# schemat.net
KiCad netlist of a schematic drawn in EAGLE
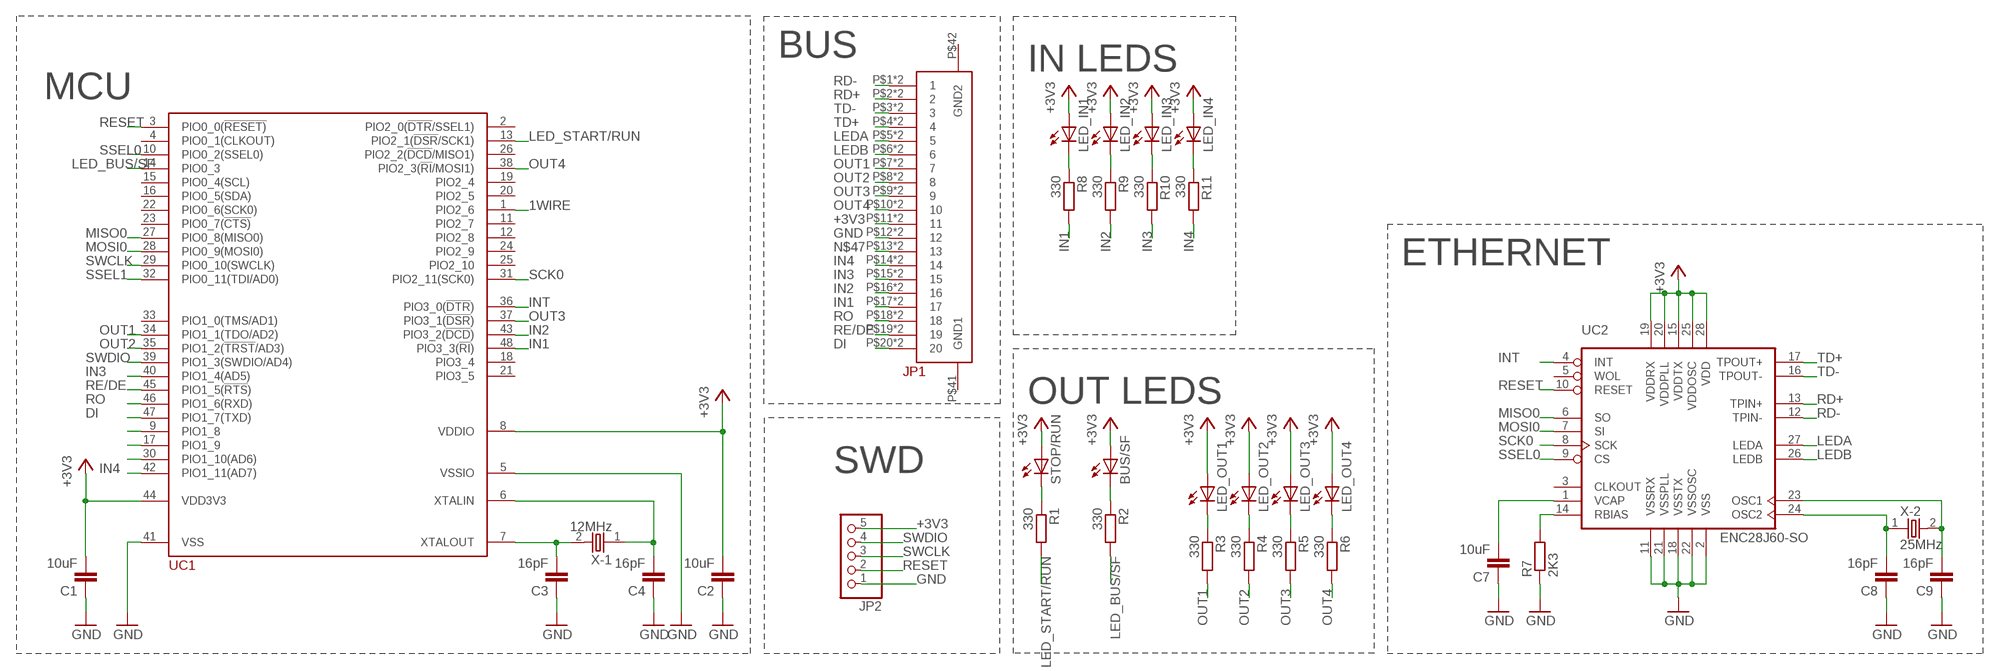
[diagram p0: schematic, sheet 1]

(export (version "E")
  (design (tool "Eeschema 10.0.6"))
  (components
    (comp (ref "BUS/SF")
      (value "LED3MM")
      (footprint "eagle-import:LED3MM")
      (libsource (lib "eagle-import") (part "LED3MM"))
    )
    (comp (ref "C1")
      (value "10uF")
      (footprint "eagle-import:C0805")
      (libsource (lib "eagle-import") (part "C-0805"))
    )
    (comp (ref "C2")
      (value "10uF")
      (footprint "eagle-import:C0805")
      (libsource (lib "eagle-import") (part "C-0805"))
    )
    (comp (ref "C3")
      (value "16pF")
      (footprint "eagle-import:C0805")
      (libsource (lib "eagle-import") (part "C-0805"))
    )
    (comp (ref "C4")
      (value "16pF")
      (footprint "eagle-import:C0805")
      (libsource (lib "eagle-import") (part "C-0805"))
    )
    (comp (ref "C7")
      (value "10uF")
      (footprint "eagle-import:C0805")
      (libsource (lib "eagle-import") (part "C-0805"))
    )
    (comp (ref "C8")
      (value "16pF")
      (footprint "eagle-import:C0805")
      (libsource (lib "eagle-import") (part "C-0805"))
    )
    (comp (ref "C9")
      (value "16pF")
      (footprint "eagle-import:C0805")
      (libsource (lib "eagle-import") (part "C-0805"))
    )
    (comp (ref "JP1")
      (value "FFC(FPC)_ZIF_20_PINV")
      (footprint "eagle-import:PCA-2C-20-V-3")
      (libsource (lib "eagle-import") (part "FFC(FPC)_ZIF_20_PINV"))
    )
    (comp (ref "JP2")
      (value "PINHD-1X5")
      (footprint "eagle-import:1X05")
      (libsource (lib "eagle-import") (part "PINHD-1X5"))
    )
    (comp (ref "LED_IN1")
      (value "LED3MM")
      (footprint "eagle-import:LED3MM")
      (libsource (lib "eagle-import") (part "LED3MM"))
    )
    (comp (ref "LED_IN2")
      (value "LED3MM")
      (footprint "eagle-import:LED3MM")
      (libsource (lib "eagle-import") (part "LED3MM"))
    )
    (comp (ref "LED_IN3")
      (value "LED3MM")
      (footprint "eagle-import:LED3MM")
      (libsource (lib "eagle-import") (part "LED3MM"))
    )
    (comp (ref "LED_IN4")
      (value "LED3MM")
      (footprint "eagle-import:LED3MM")
      (libsource (lib "eagle-import") (part "LED3MM"))
    )
    (comp (ref "LED_OUT1")
      (value "LED3MM")
      (footprint "eagle-import:LED3MM")
      (libsource (lib "eagle-import") (part "LED3MM"))
    )
    (comp (ref "LED_OUT2")
      (value "LED3MM")
      (footprint "eagle-import:LED3MM")
      (libsource (lib "eagle-import") (part "LED3MM"))
    )
    (comp (ref "LED_OUT3")
      (value "LED3MM")
      (footprint "eagle-import:LED3MM")
      (libsource (lib "eagle-import") (part "LED3MM"))
    )
    (comp (ref "LED_OUT4")
      (value "LED3MM")
      (footprint "eagle-import:LED3MM")
      (libsource (lib "eagle-import") (part "LED3MM"))
    )
    (comp (ref "R1")
      (value "330")
      (footprint "eagle-import:R0805W")
      (libsource (lib "eagle-import") (part "R-0805W"))
    )
    (comp (ref "R2")
      (value "330")
      (footprint "eagle-import:R0805W")
      (libsource (lib "eagle-import") (part "R-0805W"))
    )
    (comp (ref "R3")
      (value "330")
      (footprint "eagle-import:R0805W")
      (libsource (lib "eagle-import") (part "R-0805W"))
    )
    (comp (ref "R4")
      (value "330")
      (footprint "eagle-import:R0805W")
      (libsource (lib "eagle-import") (part "R-0805W"))
    )
    (comp (ref "R5")
      (value "330")
      (footprint "eagle-import:R0805W")
      (libsource (lib "eagle-import") (part "R-0805W"))
    )
    (comp (ref "R6")
      (value "330")
      (footprint "eagle-import:R0805W")
      (libsource (lib "eagle-import") (part "R-0805W"))
    )
    (comp (ref "R7")
      (value "2K3")
      (footprint "eagle-import:R0805")
      (libsource (lib "eagle-import") (part "R-0805"))
    )
    (comp (ref "R8")
      (value "330")
      (footprint "eagle-import:R0805W")
      (libsource (lib "eagle-import") (part "R-0805W"))
    )
    (comp (ref "R9")
      (value "330")
      (footprint "eagle-import:R0805W")
      (libsource (lib "eagle-import") (part "R-0805W"))
    )
    (comp (ref "R10")
      (value "330")
      (footprint "eagle-import:R0805W")
      (libsource (lib "eagle-import") (part "R-0805W"))
    )
    (comp (ref "R11")
      (value "330")
      (footprint "eagle-import:R0805W")
      (libsource (lib "eagle-import") (part "R-0805W"))
    )
    (comp (ref "STOP/RUN")
      (value "LED3MM")
      (footprint "eagle-import:LED3MM")
      (libsource (lib "eagle-import") (part "LED3MM"))
    )
    (comp (ref "UC1")
      (value "NXP-LPC111X")
      (footprint "eagle-import:LQFP48")
      (libsource (lib "eagle-import") (part "NXP-LPC111X"))
    )
    (comp (ref "UC2")
      (value "ENC28J60-SO")
      (footprint "eagle-import:SO28W")
      (libsource (lib "eagle-import") (part "ENC28J60-SO"))
    )
    (comp (ref "X-1")
      (value "12MHz")
      (footprint "eagle-import:HC49UP")
      (libsource (lib "eagle-import") (part "CRISTAL_SMD"))
    )
    (comp (ref "X-2")
      (value "25MHz")
      (footprint "eagle-import:HC49UP")
      (libsource (lib "eagle-import") (part "CRISTAL_SMD"))
    )
  )
  (nets
    (net (code "1") (name "+3V3") (class "Default")
      (node (ref "BUS/SF") (pin "A") (pinfunction "A_A") (pintype "passive"))
      (node (ref "C1") (pin "2") (pinfunction "2_2") (pintype "passive"))
      (node (ref "C2") (pin "2") (pinfunction "2_2") (pintype "passive"))
      (node (ref "JP1") (pin "P$11") (pinfunction "11_P$11") (pintype "bidirectional"))
      (node (ref "JP1") (pin "P$31") (pinfunction "11_P$31") (pintype "bidirectional"))
      (node (ref "JP2") (pin "5") (pinfunction "5_5") (pintype "passive"))
      (node (ref "LED_IN1") (pin "A") (pinfunction "A_A") (pintype "passive"))
      (node (ref "LED_IN2") (pin "A") (pinfunction "A_A") (pintype "passive"))
      (node (ref "LED_IN3") (pin "A") (pinfunction "A_A") (pintype "passive"))
      (node (ref "LED_IN4") (pin "A") (pinfunction "A_A") (pintype "passive"))
      (node (ref "LED_OUT1") (pin "A") (pinfunction "A_A") (pintype "passive"))
      (node (ref "LED_OUT2") (pin "A") (pinfunction "A_A") (pintype "passive"))
      (node (ref "LED_OUT3") (pin "A") (pinfunction "A_A") (pintype "passive"))
      (node (ref "LED_OUT4") (pin "A") (pinfunction "A_A") (pintype "passive"))
      (node (ref "STOP/RUN") (pin "A") (pinfunction "A_A") (pintype "passive"))
      (node (ref "UC1") (pin "44") (pinfunction "VDD3V3_44") (pintype "bidirectional"))
      (node (ref "UC1") (pin "8") (pinfunction "VDDIO_8") (pintype "bidirectional"))
      (node (ref "UC2") (pin "15") (pinfunction "VDDTX_15") (pintype "power_in"))
      (node (ref "UC2") (pin "19") (pinfunction "VDDRX_19") (pintype "power_in"))
      (node (ref "UC2") (pin "20") (pinfunction "VDDPLL_20") (pintype "power_in"))
      (node (ref "UC2") (pin "25") (pinfunction "VDDOSC_25") (pintype "power_in"))
      (node (ref "UC2") (pin "28") (pinfunction "VDD_28") (pintype "power_in"))
    )
    (net (code "2") (name "/1WIRE") (class "Default")
      (node (ref "UC1") (pin "1") (pinfunction "PIO2_6_1") (pintype "bidirectional"))
    )
    (net (code "3") (name "/DI") (class "Default")
      (node (ref "JP1") (pin "P$20") (pinfunction "20_P$20") (pintype "bidirectional"))
      (node (ref "JP1") (pin "P$40") (pinfunction "20_P$40") (pintype "bidirectional"))
      (node (ref "UC1") (pin "47") (pinfunction "PIO1_7(TXD)_47") (pintype "bidirectional"))
    )
    (net (code "4") (name "/IN1") (class "Default")
      (node (ref "JP1") (pin "P$17") (pinfunction "17_P$17") (pintype "bidirectional"))
      (node (ref "JP1") (pin "P$37") (pinfunction "17_P$37") (pintype "bidirectional"))
      (node (ref "R8") (pin "2") (pinfunction "2_2") (pintype "passive"))
      (node (ref "UC1") (pin "48") (pinfunction "PIO3_3(~{RI})_48") (pintype "bidirectional"))
    )
    (net (code "5") (name "/IN2") (class "Default")
      (node (ref "JP1") (pin "P$16") (pinfunction "16_P$16") (pintype "bidirectional"))
      (node (ref "JP1") (pin "P$36") (pinfunction "16_P$36") (pintype "bidirectional"))
      (node (ref "R9") (pin "2") (pinfunction "2_2") (pintype "passive"))
      (node (ref "UC1") (pin "43") (pinfunction "PIO3_2(~{DCD})_43") (pintype "bidirectional"))
    )
    (net (code "6") (name "/IN3") (class "Default")
      (node (ref "JP1") (pin "P$15") (pinfunction "15_P$15") (pintype "bidirectional"))
      (node (ref "JP1") (pin "P$35") (pinfunction "15_P$35") (pintype "bidirectional"))
      (node (ref "R10") (pin "2") (pinfunction "2_2") (pintype "passive"))
      (node (ref "UC1") (pin "40") (pinfunction "PIO1_4(AD5)_40") (pintype "bidirectional"))
    )
    (net (code "7") (name "/IN4") (class "Default")
      (node (ref "JP1") (pin "P$14") (pinfunction "14_P$14") (pintype "bidirectional"))
      (node (ref "JP1") (pin "P$34") (pinfunction "14_P$34") (pintype "bidirectional"))
      (node (ref "R11") (pin "2") (pinfunction "2_2") (pintype "passive"))
      (node (ref "UC1") (pin "42") (pinfunction "PIO1_11(AD7)_42") (pintype "bidirectional"))
    )
    (net (code "8") (name "/INT") (class "Default")
      (node (ref "UC1") (pin "36") (pinfunction "PIO3_0(~{DTR})_36") (pintype "bidirectional"))
      (node (ref "UC2") (pin "4") (pinfunction "INT_4") (pintype "output"))
    )
    (net (code "9") (name "/LEDA") (class "Default")
      (node (ref "JP1") (pin "P$25") (pinfunction "5_P$25") (pintype "bidirectional"))
      (node (ref "JP1") (pin "P$5") (pinfunction "5_P$5") (pintype "bidirectional"))
      (node (ref "UC2") (pin "27") (pinfunction "LEDA_27") (pintype "output"))
    )
    (net (code "10") (name "/LEDB") (class "Default")
      (node (ref "JP1") (pin "P$26") (pinfunction "6_P$26") (pintype "bidirectional"))
      (node (ref "JP1") (pin "P$6") (pinfunction "6_P$6") (pintype "bidirectional"))
      (node (ref "UC2") (pin "26") (pinfunction "LEDB_26") (pintype "output"))
    )
    (net (code "11") (name "/LED_BUS{slash}SF") (class "Default")
      (node (ref "R2") (pin "2") (pinfunction "2_2") (pintype "passive"))
      (node (ref "UC1") (pin "14") (pinfunction "PIO0_3_14") (pintype "bidirectional"))
    )
    (net (code "12") (name "/LED_START{slash}RUN") (class "Default")
      (node (ref "R1") (pin "2") (pinfunction "2_2") (pintype "passive"))
      (node (ref "UC1") (pin "13") (pinfunction "PIO2_1(~{DSR}/SCK1)_13") (pintype "bidirectional"))
    )
    (net (code "13") (name "/MISO0") (class "Default")
      (node (ref "UC1") (pin "27") (pinfunction "PIO0_8(MISO0)_27") (pintype "bidirectional"))
      (node (ref "UC2") (pin "6") (pinfunction "SO_6") (pintype "open_collector"))
    )
    (net (code "14") (name "/MOSI0") (class "Default")
      (node (ref "UC1") (pin "28") (pinfunction "PIO0_9(MOSI0)_28") (pintype "bidirectional"))
      (node (ref "UC2") (pin "7") (pinfunction "SI_7") (pintype "input"))
    )
    (net (code "15") (name "/N$47") (class "Default")
      (node (ref "JP1") (pin "P$13") (pinfunction "13_P$13") (pintype "bidirectional"))
      (node (ref "JP1") (pin "P$33") (pinfunction "13_P$33") (pintype "bidirectional"))
    )
    (net (code "16") (name "/OUT1") (class "Default")
      (node (ref "JP1") (pin "P$27") (pinfunction "7_P$27") (pintype "bidirectional"))
      (node (ref "JP1") (pin "P$7") (pinfunction "7_P$7") (pintype "bidirectional"))
      (node (ref "R3") (pin "2") (pinfunction "2_2") (pintype "passive"))
      (node (ref "UC1") (pin "34") (pinfunction "PIO1_1(TDO/AD2)_34") (pintype "bidirectional"))
    )
    (net (code "17") (name "/OUT2") (class "Default")
      (node (ref "JP1") (pin "P$28") (pinfunction "8_P$28") (pintype "bidirectional"))
      (node (ref "JP1") (pin "P$8") (pinfunction "8_P$8") (pintype "bidirectional"))
      (node (ref "R4") (pin "2") (pinfunction "2_2") (pintype "passive"))
      (node (ref "UC1") (pin "35") (pinfunction "PIO1_2(~{TRST}/AD3)_35") (pintype "bidirectional"))
    )
    (net (code "18") (name "/OUT3") (class "Default")
      (node (ref "JP1") (pin "P$29") (pinfunction "9_P$29") (pintype "bidirectional"))
      (node (ref "JP1") (pin "P$9") (pinfunction "9_P$9") (pintype "bidirectional"))
      (node (ref "R5") (pin "2") (pinfunction "2_2") (pintype "passive"))
      (node (ref "UC1") (pin "37") (pinfunction "PIO3_1(~{DSR})_37") (pintype "bidirectional"))
    )
    (net (code "19") (name "/OUT4") (class "Default")
      (node (ref "JP1") (pin "P$10") (pinfunction "10_P$10") (pintype "bidirectional"))
      (node (ref "JP1") (pin "P$30") (pinfunction "10_P$30") (pintype "bidirectional"))
      (node (ref "R6") (pin "2") (pinfunction "2_2") (pintype "passive"))
      (node (ref "UC1") (pin "38") (pinfunction "PIO2_3(~{RI}/MOSI1)_38") (pintype "bidirectional"))
    )
    (net (code "20") (name "/RD+") (class "Default")
      (node (ref "JP1") (pin "P$2") (pinfunction "2_P$2") (pintype "bidirectional"))
      (node (ref "JP1") (pin "P$22") (pinfunction "2_P$22") (pintype "bidirectional"))
      (node (ref "UC2") (pin "13") (pinfunction "TPIN+_13") (pintype "input"))
    )
    (net (code "21") (name "/RD-") (class "Default")
      (node (ref "JP1") (pin "P$1") (pinfunction "1_P$1") (pintype "bidirectional"))
      (node (ref "JP1") (pin "P$21") (pinfunction "1_P$21") (pintype "bidirectional"))
      (node (ref "UC2") (pin "12") (pinfunction "TPIN-_12") (pintype "input"))
    )
    (net (code "22") (name "/RESET") (class "Default")
      (node (ref "JP2") (pin "2") (pinfunction "2_2") (pintype "passive"))
      (node (ref "UC1") (pin "3") (pinfunction "PIO0_0(~{RESET})_3") (pintype "bidirectional"))
      (node (ref "UC2") (pin "10") (pinfunction "RESET_10") (pintype "input"))
    )
    (net (code "23") (name "/RE{slash}DE") (class "Default")
      (node (ref "JP1") (pin "P$19") (pinfunction "19_P$19") (pintype "bidirectional"))
      (node (ref "JP1") (pin "P$39") (pinfunction "19_P$39") (pintype "bidirectional"))
      (node (ref "UC1") (pin "45") (pinfunction "PIO1_5(~{RTS})_45") (pintype "bidirectional"))
    )
    (net (code "24") (name "/RO") (class "Default")
      (node (ref "JP1") (pin "P$18") (pinfunction "18_P$18") (pintype "bidirectional"))
      (node (ref "JP1") (pin "P$38") (pinfunction "18_P$38") (pintype "bidirectional"))
      (node (ref "UC1") (pin "46") (pinfunction "PIO1_6(RXD)_46") (pintype "bidirectional"))
    )
    (net (code "25") (name "/SCK0") (class "Default")
      (node (ref "UC1") (pin "31") (pinfunction "PIO2_11(SCK0)_31") (pintype "bidirectional"))
      (node (ref "UC2") (pin "8") (pinfunction "SCK_8") (pintype "input"))
    )
    (net (code "26") (name "/SSEL0") (class "Default")
      (node (ref "UC1") (pin "10") (pinfunction "PIO0_2(SSEL0)_10") (pintype "bidirectional"))
      (node (ref "UC2") (pin "9") (pinfunction "CS_9") (pintype "input"))
    )
    (net (code "27") (name "/SSEL1") (class "Default")
      (node (ref "UC1") (pin "32") (pinfunction "PIO0_11(TDI/AD0)_32") (pintype "bidirectional"))
    )
    (net (code "28") (name "/SWCLK") (class "Default")
      (node (ref "JP2") (pin "3") (pinfunction "3_3") (pintype "passive"))
      (node (ref "UC1") (pin "29") (pinfunction "PIO0_10(SWCLK)_29") (pintype "bidirectional"))
    )
    (net (code "29") (name "/SWDIO") (class "Default")
      (node (ref "JP2") (pin "4") (pinfunction "4_4") (pintype "passive"))
      (node (ref "UC1") (pin "39") (pinfunction "PIO1_3(SWDIO/AD4)_39") (pintype "bidirectional"))
    )
    (net (code "30") (name "/TD+") (class "Default")
      (node (ref "JP1") (pin "P$24") (pinfunction "4_P$24") (pintype "bidirectional"))
      (node (ref "JP1") (pin "P$4") (pinfunction "4_P$4") (pintype "bidirectional"))
      (node (ref "UC2") (pin "17") (pinfunction "TPOUT+_17") (pintype "output"))
    )
    (net (code "31") (name "/TD-") (class "Default")
      (node (ref "JP1") (pin "P$23") (pinfunction "3_P$23") (pintype "bidirectional"))
      (node (ref "JP1") (pin "P$3") (pinfunction "3_P$3") (pintype "bidirectional"))
      (node (ref "UC2") (pin "16") (pinfunction "TPOUT-_16") (pintype "output"))
    )
    (net (code "32") (name "GND") (class "Default")
      (node (ref "C1") (pin "1") (pinfunction "1_1") (pintype "passive"))
      (node (ref "C2") (pin "1") (pinfunction "1_1") (pintype "passive"))
      (node (ref "C3") (pin "1") (pinfunction "1_1") (pintype "passive"))
      (node (ref "C4") (pin "1") (pinfunction "1_1") (pintype "passive"))
      (node (ref "C7") (pin "1") (pinfunction "1_1") (pintype "passive"))
      (node (ref "C8") (pin "1") (pinfunction "1_1") (pintype "passive"))
      (node (ref "C9") (pin "1") (pinfunction "1_1") (pintype "passive"))
      (node (ref "JP1") (pin "P$12") (pinfunction "12_P$12") (pintype "bidirectional"))
      (node (ref "JP1") (pin "P$32") (pinfunction "12_P$32") (pintype "bidirectional"))
      (node (ref "JP2") (pin "1") (pinfunction "1_1") (pintype "passive"))
      (node (ref "R7") (pin "1") (pinfunction "1_1") (pintype "passive"))
      (node (ref "UC1") (pin "41") (pinfunction "VSS_41") (pintype "bidirectional"))
      (node (ref "UC1") (pin "5") (pinfunction "VSSIO_5") (pintype "bidirectional"))
      (node (ref "UC2") (pin "11") (pinfunction "VSSRX_11") (pintype "power_in"))
      (node (ref "UC2") (pin "18") (pinfunction "VSSTX_18") (pintype "power_in"))
      (node (ref "UC2") (pin "2") (pinfunction "VSS_2") (pintype "power_in"))
      (node (ref "UC2") (pin "21") (pinfunction "VSSPLL_21") (pintype "power_in"))
      (node (ref "UC2") (pin "22") (pinfunction "VSSOSC_22") (pintype "power_in"))
    )
    (net (code "33") (name "Net-(BUS/SF-C)") (class "Default")
      (node (ref "BUS/SF") (pin "K") (pinfunction "C_K") (pintype "passive"))
      (node (ref "R2") (pin "1") (pinfunction "1_1") (pintype "passive"))
    )
    (net (code "34") (name "Net-(LED_IN1-C)") (class "Default")
      (node (ref "LED_IN1") (pin "K") (pinfunction "C_K") (pintype "passive"))
      (node (ref "R8") (pin "1") (pinfunction "1_1") (pintype "passive"))
    )
    (net (code "35") (name "Net-(LED_IN2-C)") (class "Default")
      (node (ref "LED_IN2") (pin "K") (pinfunction "C_K") (pintype "passive"))
      (node (ref "R9") (pin "1") (pinfunction "1_1") (pintype "passive"))
    )
    (net (code "36") (name "Net-(LED_IN3-C)") (class "Default")
      (node (ref "LED_IN3") (pin "K") (pinfunction "C_K") (pintype "passive"))
      (node (ref "R10") (pin "1") (pinfunction "1_1") (pintype "passive"))
    )
    (net (code "37") (name "Net-(LED_IN4-C)") (class "Default")
      (node (ref "LED_IN4") (pin "K") (pinfunction "C_K") (pintype "passive"))
      (node (ref "R11") (pin "1") (pinfunction "1_1") (pintype "passive"))
    )
    (net (code "38") (name "Net-(LED_OUT1-C)") (class "Default")
      (node (ref "LED_OUT1") (pin "K") (pinfunction "C_K") (pintype "passive"))
      (node (ref "R3") (pin "1") (pinfunction "1_1") (pintype "passive"))
    )
    (net (code "39") (name "Net-(LED_OUT2-C)") (class "Default")
      (node (ref "LED_OUT2") (pin "K") (pinfunction "C_K") (pintype "passive"))
      (node (ref "R4") (pin "1") (pinfunction "1_1") (pintype "passive"))
    )
    (net (code "40") (name "Net-(LED_OUT3-C)") (class "Default")
      (node (ref "LED_OUT3") (pin "K") (pinfunction "C_K") (pintype "passive"))
      (node (ref "R5") (pin "1") (pinfunction "1_1") (pintype "passive"))
    )
    (net (code "41") (name "Net-(LED_OUT4-C)") (class "Default")
      (node (ref "LED_OUT4") (pin "K") (pinfunction "C_K") (pintype "passive"))
      (node (ref "R6") (pin "1") (pinfunction "1_1") (pintype "passive"))
    )
    (net (code "42") (name "Net-(STOP/RUN-C)") (class "Default")
      (node (ref "R1") (pin "1") (pinfunction "1_1") (pintype "passive"))
      (node (ref "STOP/RUN") (pin "K") (pinfunction "C_K") (pintype "passive"))
    )
    (net (code "43") (name "Net-(UC1-XTALIN)") (class "Default")
      (node (ref "C4") (pin "2") (pinfunction "2_2") (pintype "passive"))
      (node (ref "UC1") (pin "6") (pinfunction "XTALIN_6") (pintype "bidirectional"))
      (node (ref "X-1") (pin "1") (pinfunction "1_1") (pintype "passive"))
    )
    (net (code "44") (name "Net-(UC1-XTALOUT)") (class "Default")
      (node (ref "C3") (pin "2") (pinfunction "2_2") (pintype "passive"))
      (node (ref "UC1") (pin "7") (pinfunction "XTALOUT_7") (pintype "bidirectional"))
      (node (ref "X-1") (pin "2") (pinfunction "2_2") (pintype "passive"))
    )
    (net (code "45") (name "Net-(UC2-OSC1)") (class "Default")
      (node (ref "C9") (pin "2") (pinfunction "2_2") (pintype "passive"))
      (node (ref "UC2") (pin "23") (pinfunction "OSC1_23") (pintype "input"))
      (node (ref "X-2") (pin "2") (pinfunction "2_2") (pintype "passive"))
    )
    (net (code "46") (name "Net-(UC2-OSC2)") (class "Default")
      (node (ref "C8") (pin "2") (pinfunction "2_2") (pintype "passive"))
      (node (ref "UC2") (pin "24") (pinfunction "OSC2_24") (pintype "output"))
      (node (ref "X-2") (pin "1") (pinfunction "1_1") (pintype "passive"))
    )
    (net (code "47") (name "Net-(UC2-RBIAS)") (class "Default")
      (node (ref "R7") (pin "2") (pinfunction "2_2") (pintype "passive"))
      (node (ref "UC2") (pin "14") (pinfunction "RBIAS_14") (pintype "passive"))
    )
    (net (code "48") (name "Net-(UC2-VCAP)") (class "Default")
      (node (ref "C7") (pin "2") (pinfunction "2_2") (pintype "passive"))
      (node (ref "UC2") (pin "1") (pinfunction "VCAP_1") (pintype "power_in"))
    )
    (net (code "49") (name "unconnected-(JP1-GND1-PadP$41)") (class "Default")
      (node (ref "JP1") (pin "P$41") (pinfunction "GND1_P$41") (pintype "bidirectional"))
    )
    (net (code "50") (name "unconnected-(JP1-GND2-PadP$42)") (class "Default")
      (node (ref "JP1") (pin "P$42") (pinfunction "GND2_P$42") (pintype "bidirectional"))
    )
    (net (code "51") (name "unconnected-(UC1-PIO0_1(CLKOUT)-Pad4)") (class "Default")
      (node (ref "UC1") (pin "4") (pinfunction "PIO0_1(CLKOUT)_4") (pintype "bidirectional"))
    )
    (net (code "52") (name "unconnected-(UC1-PIO0_4(SCL)-Pad15)") (class "Default")
      (node (ref "UC1") (pin "15") (pinfunction "PIO0_4(SCL)_15") (pintype "bidirectional"))
    )
    (net (code "53") (name "unconnected-(UC1-PIO0_5(SDA)-Pad16)") (class "Default")
      (node (ref "UC1") (pin "16") (pinfunction "PIO0_5(SDA)_16") (pintype "bidirectional"))
    )
    (net (code "54") (name "unconnected-(UC1-PIO0_6(SCK0)-Pad22)") (class "Default")
      (node (ref "UC1") (pin "22") (pinfunction "PIO0_6(SCK0)_22") (pintype "bidirectional"))
    )
    (net (code "55") (name "unconnected-(UC1-PIO0_7(~{CTS})-Pad23)") (class "Default")
      (node (ref "UC1") (pin "23") (pinfunction "PIO0_7(~{CTS})_23") (pintype "bidirectional"))
    )
    (net (code "56") (name "unconnected-(UC1-PIO1_0(TMS{slash}AD1)-Pad33)") (class "Default")
      (node (ref "UC1") (pin "33") (pinfunction "PIO1_0(TMS/AD1)_33") (pintype "bidirectional"))
    )
    (net (code "57") (name "unconnected-(UC1-PIO1_8-Pad9)") (class "Default")
      (node (ref "UC1") (pin "9") (pinfunction "PIO1_8_9") (pintype "bidirectional"))
    )
    (net (code "58") (name "unconnected-(UC1-PIO1_9-Pad17)") (class "Default")
      (node (ref "UC1") (pin "17") (pinfunction "PIO1_9_17") (pintype "bidirectional"))
    )
    (net (code "59") (name "unconnected-(UC1-PIO1_10(AD6)-Pad30)") (class "Default")
      (node (ref "UC1") (pin "30") (pinfunction "PIO1_10(AD6)_30") (pintype "bidirectional"))
    )
    (net (code "60") (name "unconnected-(UC1-PIO2_0(~{DTR}{slash}SSEL1)-Pad2)") (class "Default")
      (node (ref "UC1") (pin "2") (pinfunction "PIO2_0(~{DTR}/SSEL1)_2") (pintype "bidirectional"))
    )
    (net (code "61") (name "unconnected-(UC1-PIO2_2(~{DCD}{slash}MISO1)-Pad26)") (class "Default")
      (node (ref "UC1") (pin "26") (pinfunction "PIO2_2(~{DCD}/MISO1)_26") (pintype "bidirectional"))
    )
    (net (code "62") (name "unconnected-(UC1-PIO2_4-Pad19)") (class "Default")
      (node (ref "UC1") (pin "19") (pinfunction "PIO2_4_19") (pintype "bidirectional"))
    )
    (net (code "63") (name "unconnected-(UC1-PIO2_5-Pad20)") (class "Default")
      (node (ref "UC1") (pin "20") (pinfunction "PIO2_5_20") (pintype "bidirectional"))
    )
    (net (code "64") (name "unconnected-(UC1-PIO2_7-Pad11)") (class "Default")
      (node (ref "UC1") (pin "11") (pinfunction "PIO2_7_11") (pintype "bidirectional"))
    )
    (net (code "65") (name "unconnected-(UC1-PIO2_8-Pad12)") (class "Default")
      (node (ref "UC1") (pin "12") (pinfunction "PIO2_8_12") (pintype "bidirectional"))
    )
    (net (code "66") (name "unconnected-(UC1-PIO2_9-Pad24)") (class "Default")
      (node (ref "UC1") (pin "24") (pinfunction "PIO2_9_24") (pintype "bidirectional"))
    )
    (net (code "67") (name "unconnected-(UC1-PIO2_10-Pad25)") (class "Default")
      (node (ref "UC1") (pin "25") (pinfunction "PIO2_10_25") (pintype "bidirectional"))
    )
    (net (code "68") (name "unconnected-(UC1-PIO3_4-Pad18)") (class "Default")
      (node (ref "UC1") (pin "18") (pinfunction "PIO3_4_18") (pintype "bidirectional"))
    )
    (net (code "69") (name "unconnected-(UC1-PIO3_5-Pad21)") (class "Default")
      (node (ref "UC1") (pin "21") (pinfunction "PIO3_5_21") (pintype "bidirectional"))
    )
    (net (code "70") (name "unconnected-(UC2-CLKOUT-Pad3)") (class "Default")
      (node (ref "UC2") (pin "3") (pinfunction "CLKOUT_3") (pintype "output"))
    )
    (net (code "71") (name "unconnected-(UC2-WOL-Pad5)") (class "Default")
      (node (ref "UC2") (pin "5") (pinfunction "WOL_5") (pintype "output"))
    )
  )
)
